# LEDs.net
KiCad netlist of a schematic drawn in Altium Designer
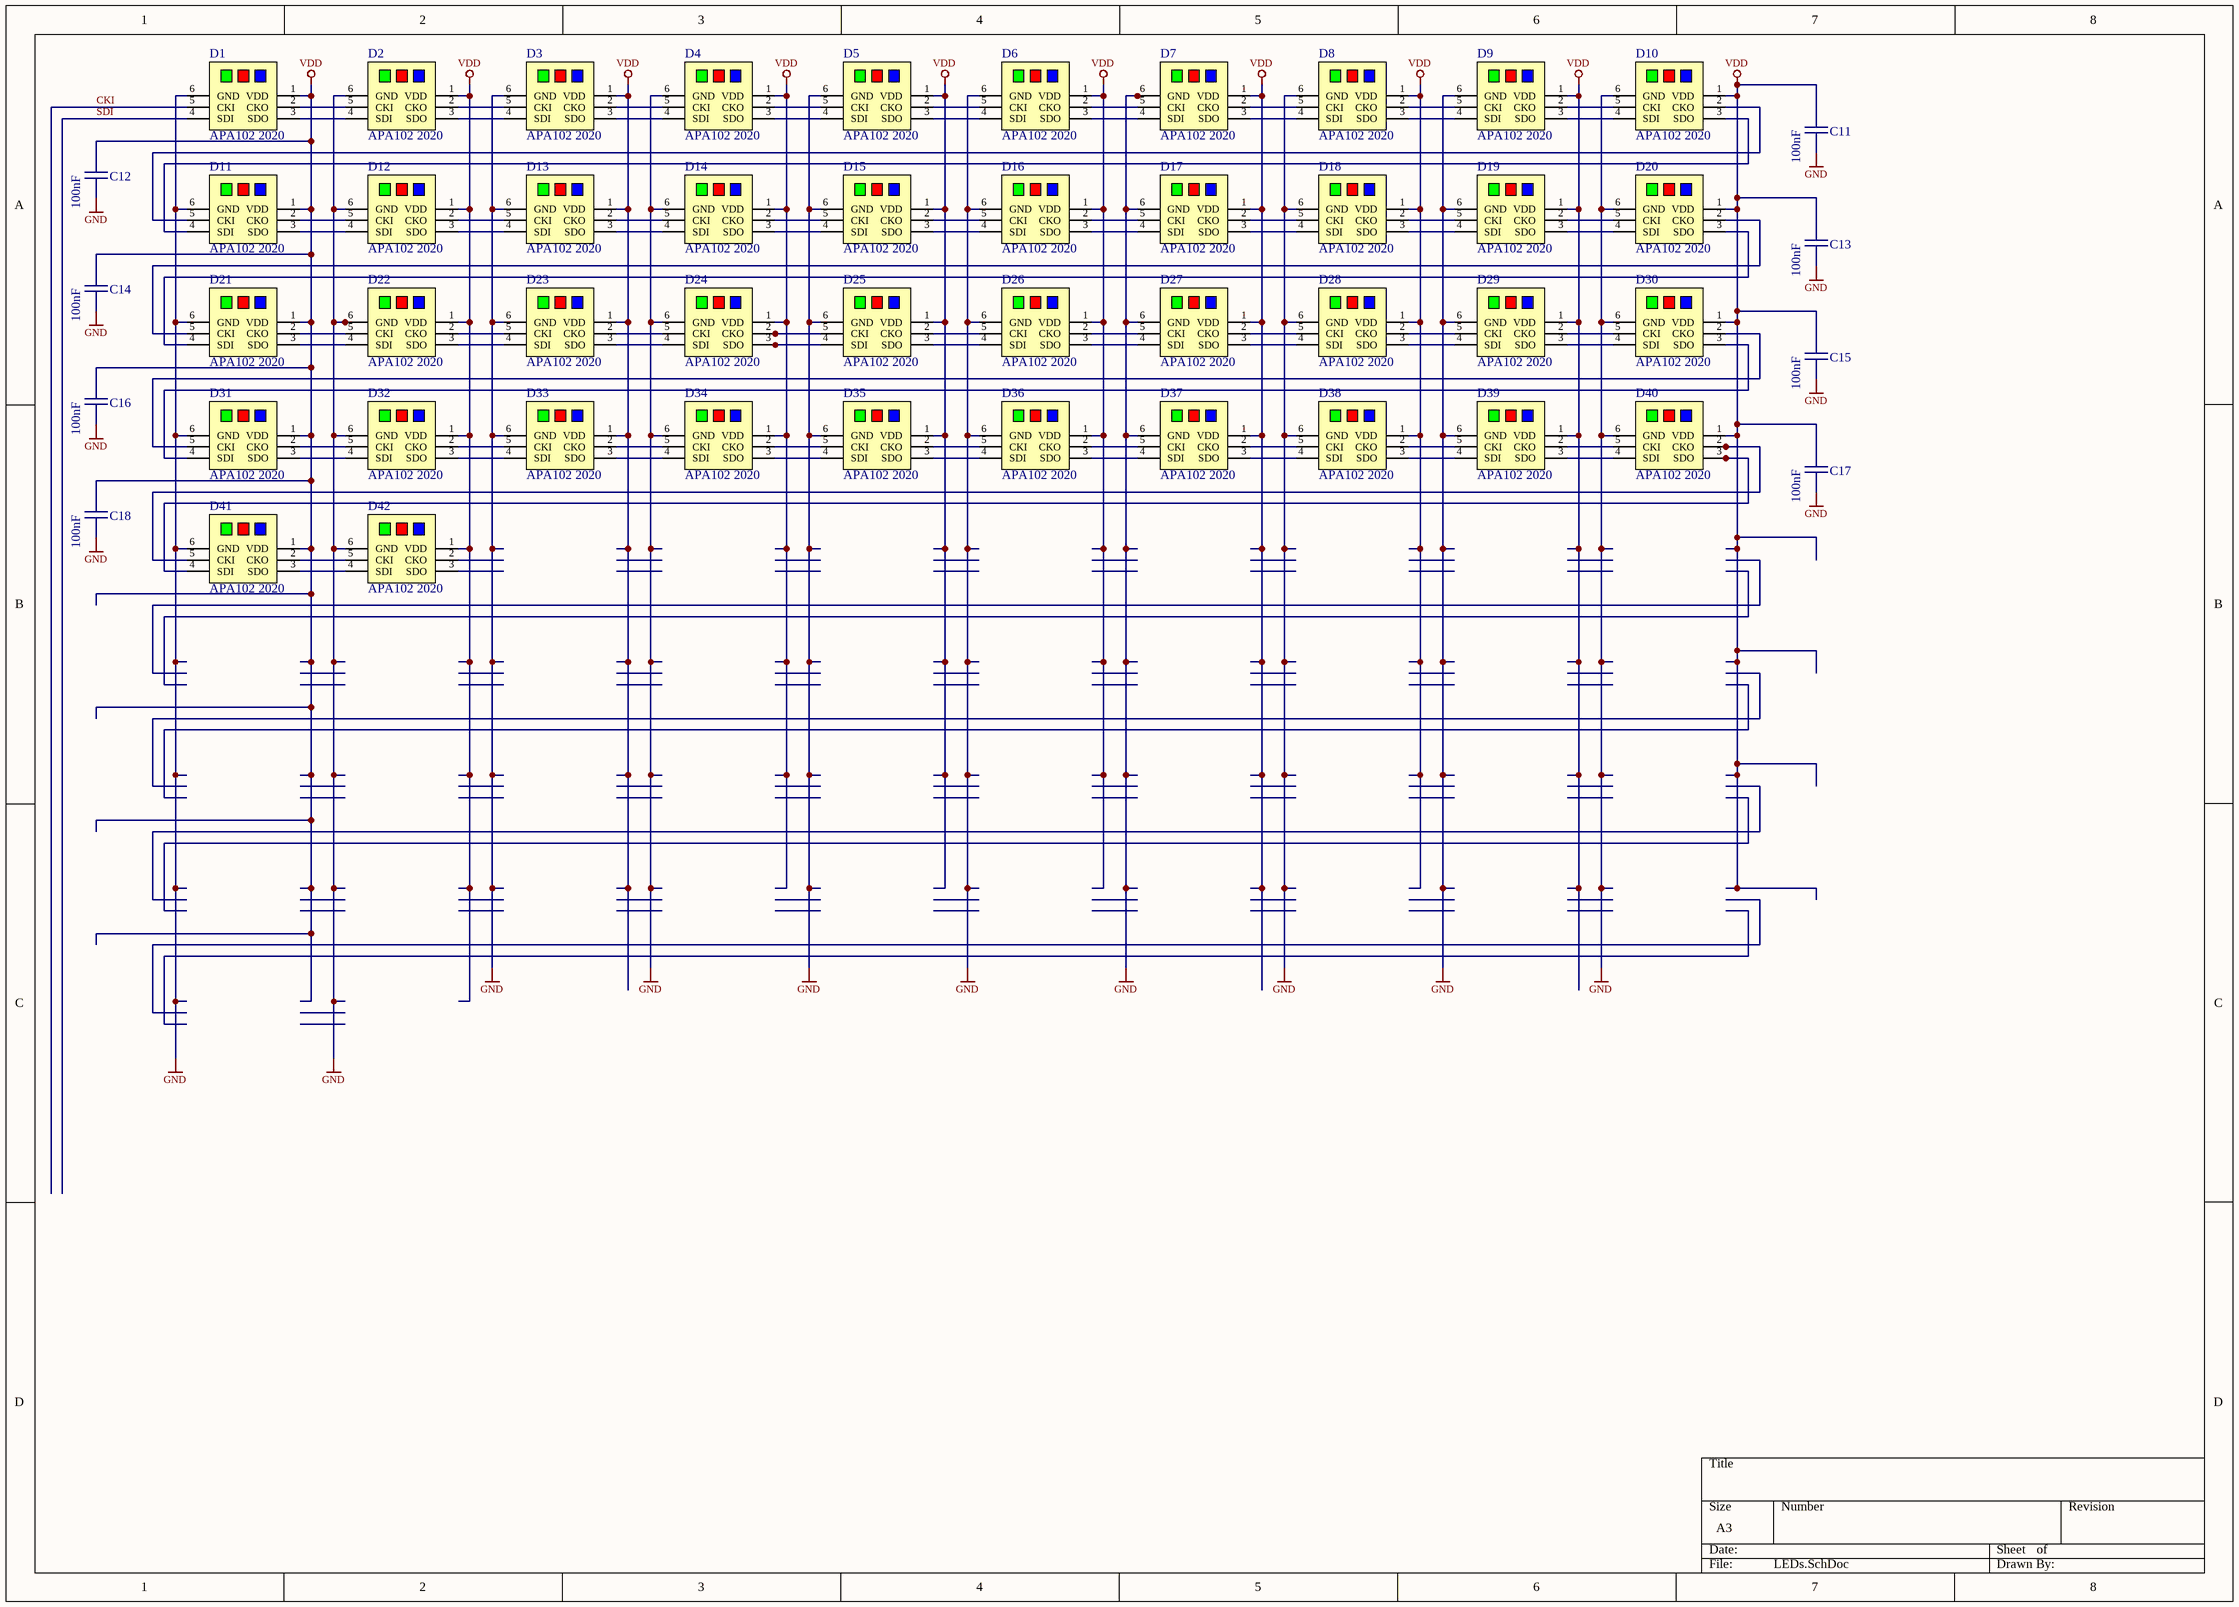
[diagram p0: LEDs.SchDoc]

(export (version "E")
  (design (tool "Eeschema 10.0.6"))
  (components
    (comp (ref "C11")
      (value "100nF")
      (footprint "CAPC0603(1608)55_N")
      (libsource (lib "OVLib_64") (part "CAP"))
    )
    (comp (ref "C12")
      (value "100nF")
      (footprint "CAPC0603(1608)55_N")
      (libsource (lib "OVLib_64") (part "CAP"))
    )
    (comp (ref "C13")
      (value "100nF")
      (footprint "CAPC0603(1608)55_N")
      (libsource (lib "OVLib_64") (part "CAP"))
    )
    (comp (ref "C14")
      (value "100nF")
      (footprint "CAPC0603(1608)55_N")
      (libsource (lib "OVLib_64") (part "CAP"))
    )
    (comp (ref "C15")
      (value "100nF")
      (footprint "CAPC0603(1608)55_N")
      (libsource (lib "OVLib_64") (part "CAP"))
    )
    (comp (ref "C16")
      (value "100nF")
      (footprint "CAPC0603(1608)55_N")
      (libsource (lib "OVLib_64") (part "CAP"))
    )
    (comp (ref "C17")
      (value "100nF")
      (footprint "CAPC0603(1608)55_N")
      (libsource (lib "OVLib_64") (part "CAP"))
    )
    (comp (ref "C18")
      (value "100nF")
      (footprint "CAPC0603(1608)55_N")
      (libsource (lib "OVLib_64") (part "CAP"))
    )
    (comp (ref "D1")
      (value "APA102 2020")
      (footprint "APA_RGB_LED_2020")
      (libsource (lib "OVLib_64") (part "LED_RGB_APA102"))
    )
    (comp (ref "D2")
      (value "APA102 2020")
      (footprint "APA_RGB_LED_2020")
      (libsource (lib "OVLib_64") (part "LED_RGB_APA102"))
    )
    (comp (ref "D3")
      (value "APA102 2020")
      (footprint "APA_RGB_LED_2020")
      (libsource (lib "OVLib_64") (part "LED_RGB_APA102"))
    )
    (comp (ref "D4")
      (value "APA102 2020")
      (footprint "APA_RGB_LED_2020")
      (libsource (lib "OVLib_64") (part "LED_RGB_APA102"))
    )
    (comp (ref "D5")
      (value "APA102 2020")
      (footprint "APA_RGB_LED_2020")
      (libsource (lib "OVLib_64") (part "LED_RGB_APA102"))
    )
    (comp (ref "D6")
      (value "APA102 2020")
      (footprint "APA_RGB_LED_2020")
      (libsource (lib "OVLib_64") (part "LED_RGB_APA102"))
    )
    (comp (ref "D7")
      (value "APA102 2020")
      (footprint "APA_RGB_LED_2020")
      (libsource (lib "OVLib_64") (part "LED_RGB_APA102"))
    )
    (comp (ref "D8")
      (value "APA102 2020")
      (footprint "APA_RGB_LED_2020")
      (libsource (lib "OVLib_64") (part "LED_RGB_APA102"))
    )
    (comp (ref "D9")
      (value "APA102 2020")
      (footprint "APA_RGB_LED_2020")
      (libsource (lib "OVLib_64") (part "LED_RGB_APA102"))
    )
    (comp (ref "D10")
      (value "APA102 2020")
      (footprint "APA_RGB_LED_2020")
      (libsource (lib "OVLib_64") (part "LED_RGB_APA102"))
    )
    (comp (ref "D11")
      (value "APA102 2020")
      (footprint "APA_RGB_LED_2020")
      (libsource (lib "OVLib_64") (part "LED_RGB_APA102"))
    )
    (comp (ref "D12")
      (value "APA102 2020")
      (footprint "APA_RGB_LED_2020")
      (libsource (lib "OVLib_64") (part "LED_RGB_APA102"))
    )
    (comp (ref "D13")
      (value "APA102 2020")
      (footprint "APA_RGB_LED_2020")
      (libsource (lib "OVLib_64") (part "LED_RGB_APA102"))
    )
    (comp (ref "D14")
      (value "APA102 2020")
      (footprint "APA_RGB_LED_2020")
      (libsource (lib "OVLib_64") (part "LED_RGB_APA102"))
    )
    (comp (ref "D15")
      (value "APA102 2020")
      (footprint "APA_RGB_LED_2020")
      (libsource (lib "OVLib_64") (part "LED_RGB_APA102"))
    )
    (comp (ref "D16")
      (value "APA102 2020")
      (footprint "APA_RGB_LED_2020")
      (libsource (lib "OVLib_64") (part "LED_RGB_APA102"))
    )
    (comp (ref "D17")
      (value "APA102 2020")
      (footprint "APA_RGB_LED_2020")
      (libsource (lib "OVLib_64") (part "LED_RGB_APA102"))
    )
    (comp (ref "D18")
      (value "APA102 2020")
      (footprint "APA_RGB_LED_2020")
      (libsource (lib "OVLib_64") (part "LED_RGB_APA102"))
    )
    (comp (ref "D19")
      (value "APA102 2020")
      (footprint "APA_RGB_LED_2020")
      (libsource (lib "OVLib_64") (part "LED_RGB_APA102"))
    )
    (comp (ref "D20")
      (value "APA102 2020")
      (footprint "APA_RGB_LED_2020")
      (libsource (lib "OVLib_64") (part "LED_RGB_APA102"))
    )
    (comp (ref "D21")
      (value "APA102 2020")
      (footprint "APA_RGB_LED_2020")
      (libsource (lib "OVLib_64") (part "LED_RGB_APA102"))
    )
    (comp (ref "D22")
      (value "APA102 2020")
      (footprint "APA_RGB_LED_2020")
      (libsource (lib "OVLib_64") (part "LED_RGB_APA102"))
    )
    (comp (ref "D23")
      (value "APA102 2020")
      (footprint "APA_RGB_LED_2020")
      (libsource (lib "OVLib_64") (part "LED_RGB_APA102"))
    )
    (comp (ref "D24")
      (value "APA102 2020")
      (footprint "APA_RGB_LED_2020")
      (libsource (lib "OVLib_64") (part "LED_RGB_APA102"))
    )
    (comp (ref "D25")
      (value "APA102 2020")
      (footprint "APA_RGB_LED_2020")
      (libsource (lib "OVLib_64") (part "LED_RGB_APA102"))
    )
    (comp (ref "D26")
      (value "APA102 2020")
      (footprint "APA_RGB_LED_2020")
      (libsource (lib "OVLib_64") (part "LED_RGB_APA102"))
    )
    (comp (ref "D27")
      (value "APA102 2020")
      (footprint "APA_RGB_LED_2020")
      (libsource (lib "OVLib_64") (part "LED_RGB_APA102"))
    )
    (comp (ref "D28")
      (value "APA102 2020")
      (footprint "APA_RGB_LED_2020")
      (libsource (lib "OVLib_64") (part "LED_RGB_APA102"))
    )
    (comp (ref "D29")
      (value "APA102 2020")
      (footprint "APA_RGB_LED_2020")
      (libsource (lib "OVLib_64") (part "LED_RGB_APA102"))
    )
    (comp (ref "D30")
      (value "APA102 2020")
      (footprint "APA_RGB_LED_2020")
      (libsource (lib "OVLib_64") (part "LED_RGB_APA102"))
    )
    (comp (ref "D31")
      (value "APA102 2020")
      (footprint "APA_RGB_LED_2020")
      (libsource (lib "OVLib_64") (part "LED_RGB_APA102"))
    )
    (comp (ref "D32")
      (value "APA102 2020")
      (footprint "APA_RGB_LED_2020")
      (libsource (lib "OVLib_64") (part "LED_RGB_APA102"))
    )
    (comp (ref "D33")
      (value "APA102 2020")
      (footprint "APA_RGB_LED_2020")
      (libsource (lib "OVLib_64") (part "LED_RGB_APA102"))
    )
    (comp (ref "D34")
      (value "APA102 2020")
      (footprint "APA_RGB_LED_2020")
      (libsource (lib "OVLib_64") (part "LED_RGB_APA102"))
    )
    (comp (ref "D35")
      (value "APA102 2020")
      (footprint "APA_RGB_LED_2020")
      (libsource (lib "OVLib_64") (part "LED_RGB_APA102"))
    )
    (comp (ref "D36")
      (value "APA102 2020")
      (footprint "APA_RGB_LED_2020")
      (libsource (lib "OVLib_64") (part "LED_RGB_APA102"))
    )
    (comp (ref "D37")
      (value "APA102 2020")
      (footprint "APA_RGB_LED_2020")
      (libsource (lib "OVLib_64") (part "LED_RGB_APA102"))
    )
    (comp (ref "D38")
      (value "APA102 2020")
      (footprint "APA_RGB_LED_2020")
      (libsource (lib "OVLib_64") (part "LED_RGB_APA102"))
    )
    (comp (ref "D39")
      (value "APA102 2020")
      (footprint "APA_RGB_LED_2020")
      (libsource (lib "OVLib_64") (part "LED_RGB_APA102"))
    )
    (comp (ref "D40")
      (value "APA102 2020")
      (footprint "APA_RGB_LED_2020")
      (libsource (lib "OVLib_64") (part "LED_RGB_APA102"))
    )
    (comp (ref "D41")
      (value "APA102 2020")
      (footprint "APA_RGB_LED_2020")
      (libsource (lib "OVLib_64") (part "LED_RGB_APA102"))
    )
    (comp (ref "D42")
      (value "APA102 2020")
      (footprint "APA_RGB_LED_2020")
      (libsource (lib "OVLib_64") (part "LED_RGB_APA102"))
    )
  )
  (nets
    (net (code "1") (name "/CKI") (class "Default")
      (node (ref "D1") (pin "5") (pinfunction "CKI_5") (pintype "passive"))
    )
    (net (code "2") (name "/SDI") (class "Default")
      (node (ref "D1") (pin "4") (pinfunction "SDI_4") (pintype "passive"))
    )
    (net (code "3") (name "GND") (class "Default")
      (node (ref "C11") (pin "1") (pinfunction "1_1") (pintype "passive"))
      (node (ref "C12") (pin "1") (pinfunction "1_1") (pintype "passive"))
      (node (ref "C13") (pin "1") (pinfunction "1_1") (pintype "passive"))
      (node (ref "C14") (pin "1") (pinfunction "1_1") (pintype "passive"))
      (node (ref "C15") (pin "1") (pinfunction "1_1") (pintype "passive"))
      (node (ref "C16") (pin "1") (pinfunction "1_1") (pintype "passive"))
      (node (ref "C17") (pin "1") (pinfunction "1_1") (pintype "passive"))
      (node (ref "C18") (pin "1") (pinfunction "1_1") (pintype "passive"))
      (node (ref "D1") (pin "6") (pinfunction "GND_6") (pintype "passive"))
      (node (ref "D10") (pin "6") (pinfunction "GND_6") (pintype "passive"))
      (node (ref "D11") (pin "6") (pinfunction "GND_6") (pintype "passive"))
      (node (ref "D12") (pin "6") (pinfunction "GND_6") (pintype "passive"))
      (node (ref "D13") (pin "6") (pinfunction "GND_6") (pintype "passive"))
      (node (ref "D14") (pin "6") (pinfunction "GND_6") (pintype "passive"))
      (node (ref "D15") (pin "6") (pinfunction "GND_6") (pintype "passive"))
      (node (ref "D16") (pin "6") (pinfunction "GND_6") (pintype "passive"))
      (node (ref "D17") (pin "6") (pinfunction "GND_6") (pintype "passive"))
      (node (ref "D18") (pin "6") (pinfunction "GND_6") (pintype "passive"))
      (node (ref "D19") (pin "6") (pinfunction "GND_6") (pintype "passive"))
      (node (ref "D2") (pin "6") (pinfunction "GND_6") (pintype "passive"))
      (node (ref "D20") (pin "6") (pinfunction "GND_6") (pintype "passive"))
      (node (ref "D21") (pin "6") (pinfunction "GND_6") (pintype "passive"))
      (node (ref "D22") (pin "6") (pinfunction "GND_6") (pintype "passive"))
      (node (ref "D23") (pin "6") (pinfunction "GND_6") (pintype "passive"))
      (node (ref "D24") (pin "6") (pinfunction "GND_6") (pintype "passive"))
      (node (ref "D25") (pin "6") (pinfunction "GND_6") (pintype "passive"))
      (node (ref "D26") (pin "6") (pinfunction "GND_6") (pintype "passive"))
      (node (ref "D27") (pin "6") (pinfunction "GND_6") (pintype "passive"))
      (node (ref "D28") (pin "6") (pinfunction "GND_6") (pintype "passive"))
      (node (ref "D29") (pin "6") (pinfunction "GND_6") (pintype "passive"))
      (node (ref "D3") (pin "6") (pinfunction "GND_6") (pintype "passive"))
      (node (ref "D30") (pin "6") (pinfunction "GND_6") (pintype "passive"))
      (node (ref "D31") (pin "6") (pinfunction "GND_6") (pintype "passive"))
      (node (ref "D32") (pin "6") (pinfunction "GND_6") (pintype "passive"))
      (node (ref "D33") (pin "6") (pinfunction "GND_6") (pintype "passive"))
      (node (ref "D34") (pin "6") (pinfunction "GND_6") (pintype "passive"))
      (node (ref "D35") (pin "6") (pinfunction "GND_6") (pintype "passive"))
      (node (ref "D36") (pin "6") (pinfunction "GND_6") (pintype "passive"))
      (node (ref "D37") (pin "6") (pinfunction "GND_6") (pintype "passive"))
      (node (ref "D38") (pin "6") (pinfunction "GND_6") (pintype "passive"))
      (node (ref "D39") (pin "6") (pinfunction "GND_6") (pintype "passive"))
      (node (ref "D4") (pin "6") (pinfunction "GND_6") (pintype "passive"))
      (node (ref "D40") (pin "6") (pinfunction "GND_6") (pintype "passive"))
      (node (ref "D41") (pin "6") (pinfunction "GND_6") (pintype "passive"))
      (node (ref "D42") (pin "6") (pinfunction "GND_6") (pintype "passive"))
      (node (ref "D5") (pin "6") (pinfunction "GND_6") (pintype "passive"))
      (node (ref "D6") (pin "6") (pinfunction "GND_6") (pintype "passive"))
      (node (ref "D7") (pin "6") (pinfunction "GND_6") (pintype "passive"))
      (node (ref "D8") (pin "6") (pinfunction "GND_6") (pintype "passive"))
      (node (ref "D9") (pin "6") (pinfunction "GND_6") (pintype "passive"))
    )
    (net (code "4") (name "Net-(D1-CKO)") (class "Default")
      (node (ref "D1") (pin "2") (pinfunction "CKO_2") (pintype "passive"))
      (node (ref "D2") (pin "5") (pinfunction "CKI_5") (pintype "passive"))
    )
    (net (code "5") (name "Net-(D1-SDO)") (class "Default")
      (node (ref "D1") (pin "3") (pinfunction "SDO_3") (pintype "passive"))
      (node (ref "D2") (pin "4") (pinfunction "SDI_4") (pintype "passive"))
    )
    (net (code "6") (name "Net-(D2-CKO)") (class "Default")
      (node (ref "D2") (pin "2") (pinfunction "CKO_2") (pintype "passive"))
      (node (ref "D3") (pin "5") (pinfunction "CKI_5") (pintype "passive"))
    )
    (net (code "7") (name "Net-(D2-SDO)") (class "Default")
      (node (ref "D2") (pin "3") (pinfunction "SDO_3") (pintype "passive"))
      (node (ref "D3") (pin "4") (pinfunction "SDI_4") (pintype "passive"))
    )
    (net (code "8") (name "Net-(D3-CKO)") (class "Default")
      (node (ref "D3") (pin "2") (pinfunction "CKO_2") (pintype "passive"))
      (node (ref "D4") (pin "5") (pinfunction "CKI_5") (pintype "passive"))
    )
    (net (code "9") (name "Net-(D3-SDO)") (class "Default")
      (node (ref "D3") (pin "3") (pinfunction "SDO_3") (pintype "passive"))
      (node (ref "D4") (pin "4") (pinfunction "SDI_4") (pintype "passive"))
    )
    (net (code "10") (name "Net-(D4-CKO)") (class "Default")
      (node (ref "D4") (pin "2") (pinfunction "CKO_2") (pintype "passive"))
      (node (ref "D5") (pin "5") (pinfunction "CKI_5") (pintype "passive"))
    )
    (net (code "11") (name "Net-(D4-SDO)") (class "Default")
      (node (ref "D4") (pin "3") (pinfunction "SDO_3") (pintype "passive"))
      (node (ref "D5") (pin "4") (pinfunction "SDI_4") (pintype "passive"))
    )
    (net (code "12") (name "Net-(D5-CKO)") (class "Default")
      (node (ref "D5") (pin "2") (pinfunction "CKO_2") (pintype "passive"))
      (node (ref "D6") (pin "5") (pinfunction "CKI_5") (pintype "passive"))
    )
    (net (code "13") (name "Net-(D5-SDO)") (class "Default")
      (node (ref "D5") (pin "3") (pinfunction "SDO_3") (pintype "passive"))
      (node (ref "D6") (pin "4") (pinfunction "SDI_4") (pintype "passive"))
    )
    (net (code "14") (name "Net-(D6-CKO)") (class "Default")
      (node (ref "D6") (pin "2") (pinfunction "CKO_2") (pintype "passive"))
      (node (ref "D7") (pin "5") (pinfunction "CKI_5") (pintype "passive"))
    )
    (net (code "15") (name "Net-(D6-SDO)") (class "Default")
      (node (ref "D6") (pin "3") (pinfunction "SDO_3") (pintype "passive"))
      (node (ref "D7") (pin "4") (pinfunction "SDI_4") (pintype "passive"))
    )
    (net (code "16") (name "Net-(D7-CKO)") (class "Default")
      (node (ref "D7") (pin "2") (pinfunction "CKO_2") (pintype "passive"))
      (node (ref "D8") (pin "5") (pinfunction "CKI_5") (pintype "passive"))
    )
    (net (code "17") (name "Net-(D7-SDO)") (class "Default")
      (node (ref "D7") (pin "3") (pinfunction "SDO_3") (pintype "passive"))
      (node (ref "D8") (pin "4") (pinfunction "SDI_4") (pintype "passive"))
    )
    (net (code "18") (name "Net-(D8-CKO)") (class "Default")
      (node (ref "D8") (pin "2") (pinfunction "CKO_2") (pintype "passive"))
      (node (ref "D9") (pin "5") (pinfunction "CKI_5") (pintype "passive"))
    )
    (net (code "19") (name "Net-(D8-SDO)") (class "Default")
      (node (ref "D8") (pin "3") (pinfunction "SDO_3") (pintype "passive"))
      (node (ref "D9") (pin "4") (pinfunction "SDI_4") (pintype "passive"))
    )
    (net (code "20") (name "Net-(D10-CKI)") (class "Default")
      (node (ref "D10") (pin "5") (pinfunction "CKI_5") (pintype "passive"))
      (node (ref "D9") (pin "2") (pinfunction "CKO_2") (pintype "passive"))
    )
    (net (code "21") (name "Net-(D10-CKO)") (class "Default")
      (node (ref "D10") (pin "2") (pinfunction "CKO_2") (pintype "passive"))
      (node (ref "D11") (pin "5") (pinfunction "CKI_5") (pintype "passive"))
    )
    (net (code "22") (name "Net-(D10-SDI)") (class "Default")
      (node (ref "D10") (pin "4") (pinfunction "SDI_4") (pintype "passive"))
      (node (ref "D9") (pin "3") (pinfunction "SDO_3") (pintype "passive"))
    )
    (net (code "23") (name "Net-(D10-SDO)") (class "Default")
      (node (ref "D10") (pin "3") (pinfunction "SDO_3") (pintype "passive"))
      (node (ref "D11") (pin "4") (pinfunction "SDI_4") (pintype "passive"))
    )
    (net (code "24") (name "Net-(D11-CKO)") (class "Default")
      (node (ref "D11") (pin "2") (pinfunction "CKO_2") (pintype "passive"))
      (node (ref "D12") (pin "5") (pinfunction "CKI_5") (pintype "passive"))
    )
    (net (code "25") (name "Net-(D11-SDO)") (class "Default")
      (node (ref "D11") (pin "3") (pinfunction "SDO_3") (pintype "passive"))
      (node (ref "D12") (pin "4") (pinfunction "SDI_4") (pintype "passive"))
    )
    (net (code "26") (name "Net-(D12-CKO)") (class "Default")
      (node (ref "D12") (pin "2") (pinfunction "CKO_2") (pintype "passive"))
      (node (ref "D13") (pin "5") (pinfunction "CKI_5") (pintype "passive"))
    )
    (net (code "27") (name "Net-(D12-SDO)") (class "Default")
      (node (ref "D12") (pin "3") (pinfunction "SDO_3") (pintype "passive"))
      (node (ref "D13") (pin "4") (pinfunction "SDI_4") (pintype "passive"))
    )
    (net (code "28") (name "Net-(D13-CKO)") (class "Default")
      (node (ref "D13") (pin "2") (pinfunction "CKO_2") (pintype "passive"))
      (node (ref "D14") (pin "5") (pinfunction "CKI_5") (pintype "passive"))
    )
    (net (code "29") (name "Net-(D13-SDO)") (class "Default")
      (node (ref "D13") (pin "3") (pinfunction "SDO_3") (pintype "passive"))
      (node (ref "D14") (pin "4") (pinfunction "SDI_4") (pintype "passive"))
    )
    (net (code "30") (name "Net-(D14-CKO)") (class "Default")
      (node (ref "D14") (pin "2") (pinfunction "CKO_2") (pintype "passive"))
      (node (ref "D15") (pin "5") (pinfunction "CKI_5") (pintype "passive"))
    )
    (net (code "31") (name "Net-(D14-SDO)") (class "Default")
      (node (ref "D14") (pin "3") (pinfunction "SDO_3") (pintype "passive"))
      (node (ref "D15") (pin "4") (pinfunction "SDI_4") (pintype "passive"))
    )
    (net (code "32") (name "Net-(D15-CKO)") (class "Default")
      (node (ref "D15") (pin "2") (pinfunction "CKO_2") (pintype "passive"))
      (node (ref "D16") (pin "5") (pinfunction "CKI_5") (pintype "passive"))
    )
    (net (code "33") (name "Net-(D15-SDO)") (class "Default")
      (node (ref "D15") (pin "3") (pinfunction "SDO_3") (pintype "passive"))
      (node (ref "D16") (pin "4") (pinfunction "SDI_4") (pintype "passive"))
    )
    (net (code "34") (name "Net-(D16-CKO)") (class "Default")
      (node (ref "D16") (pin "2") (pinfunction "CKO_2") (pintype "passive"))
      (node (ref "D17") (pin "5") (pinfunction "CKI_5") (pintype "passive"))
    )
    (net (code "35") (name "Net-(D16-SDO)") (class "Default")
      (node (ref "D16") (pin "3") (pinfunction "SDO_3") (pintype "passive"))
      (node (ref "D17") (pin "4") (pinfunction "SDI_4") (pintype "passive"))
    )
    (net (code "36") (name "Net-(D17-CKO)") (class "Default")
      (node (ref "D17") (pin "2") (pinfunction "CKO_2") (pintype "passive"))
      (node (ref "D18") (pin "5") (pinfunction "CKI_5") (pintype "passive"))
    )
    (net (code "37") (name "Net-(D17-SDO)") (class "Default")
      (node (ref "D17") (pin "3") (pinfunction "SDO_3") (pintype "passive"))
      (node (ref "D18") (pin "4") (pinfunction "SDI_4") (pintype "passive"))
    )
    (net (code "38") (name "Net-(D18-CKO)") (class "Default")
      (node (ref "D18") (pin "2") (pinfunction "CKO_2") (pintype "passive"))
      (node (ref "D19") (pin "5") (pinfunction "CKI_5") (pintype "passive"))
    )
    (net (code "39") (name "Net-(D18-SDO)") (class "Default")
      (node (ref "D18") (pin "3") (pinfunction "SDO_3") (pintype "passive"))
      (node (ref "D19") (pin "4") (pinfunction "SDI_4") (pintype "passive"))
    )
    (net (code "40") (name "Net-(D19-CKO)") (class "Default")
      (node (ref "D19") (pin "2") (pinfunction "CKO_2") (pintype "passive"))
      (node (ref "D20") (pin "5") (pinfunction "CKI_5") (pintype "passive"))
    )
    (net (code "41") (name "Net-(D19-SDO)") (class "Default")
      (node (ref "D19") (pin "3") (pinfunction "SDO_3") (pintype "passive"))
      (node (ref "D20") (pin "4") (pinfunction "SDI_4") (pintype "passive"))
    )
    (net (code "42") (name "Net-(D20-CKO)") (class "Default")
      (node (ref "D20") (pin "2") (pinfunction "CKO_2") (pintype "passive"))
      (node (ref "D21") (pin "5") (pinfunction "CKI_5") (pintype "passive"))
    )
    (net (code "43") (name "Net-(D20-SDO)") (class "Default")
      (node (ref "D20") (pin "3") (pinfunction "SDO_3") (pintype "passive"))
      (node (ref "D21") (pin "4") (pinfunction "SDI_4") (pintype "passive"))
    )
    (net (code "44") (name "Net-(D21-CKO)") (class "Default")
      (node (ref "D21") (pin "2") (pinfunction "CKO_2") (pintype "passive"))
      (node (ref "D22") (pin "5") (pinfunction "CKI_5") (pintype "passive"))
    )
    (net (code "45") (name "Net-(D21-SDO)") (class "Default")
      (node (ref "D21") (pin "3") (pinfunction "SDO_3") (pintype "passive"))
      (node (ref "D22") (pin "4") (pinfunction "SDI_4") (pintype "passive"))
    )
    (net (code "46") (name "Net-(D22-CKO)") (class "Default")
      (node (ref "D22") (pin "2") (pinfunction "CKO_2") (pintype "passive"))
      (node (ref "D23") (pin "5") (pinfunction "CKI_5") (pintype "passive"))
    )
    (net (code "47") (name "Net-(D22-SDO)") (class "Default")
      (node (ref "D22") (pin "3") (pinfunction "SDO_3") (pintype "passive"))
      (node (ref "D23") (pin "4") (pinfunction "SDI_4") (pintype "passive"))
    )
    (net (code "48") (name "Net-(D23-CKO)") (class "Default")
      (node (ref "D23") (pin "2") (pinfunction "CKO_2") (pintype "passive"))
      (node (ref "D24") (pin "5") (pinfunction "CKI_5") (pintype "passive"))
    )
    (net (code "49") (name "Net-(D23-SDO)") (class "Default")
      (node (ref "D23") (pin "3") (pinfunction "SDO_3") (pintype "passive"))
      (node (ref "D24") (pin "4") (pinfunction "SDI_4") (pintype "passive"))
    )
    (net (code "50") (name "Net-(D24-CKO)") (class "Default")
      (node (ref "D24") (pin "2") (pinfunction "CKO_2") (pintype "passive"))
      (node (ref "D25") (pin "5") (pinfunction "CKI_5") (pintype "passive"))
    )
    (net (code "51") (name "Net-(D24-SDO)") (class "Default")
      (node (ref "D24") (pin "3") (pinfunction "SDO_3") (pintype "passive"))
      (node (ref "D25") (pin "4") (pinfunction "SDI_4") (pintype "passive"))
    )
    (net (code "52") (name "Net-(D25-CKO)") (class "Default")
      (node (ref "D25") (pin "2") (pinfunction "CKO_2") (pintype "passive"))
      (node (ref "D26") (pin "5") (pinfunction "CKI_5") (pintype "passive"))
    )
    (net (code "53") (name "Net-(D25-SDO)") (class "Default")
      (node (ref "D25") (pin "3") (pinfunction "SDO_3") (pintype "passive"))
      (node (ref "D26") (pin "4") (pinfunction "SDI_4") (pintype "passive"))
    )
    (net (code "54") (name "Net-(D26-CKO)") (class "Default")
      (node (ref "D26") (pin "2") (pinfunction "CKO_2") (pintype "passive"))
      (node (ref "D27") (pin "5") (pinfunction "CKI_5") (pintype "passive"))
    )
    (net (code "55") (name "Net-(D26-SDO)") (class "Default")
      (node (ref "D26") (pin "3") (pinfunction "SDO_3") (pintype "passive"))
      (node (ref "D27") (pin "4") (pinfunction "SDI_4") (pintype "passive"))
    )
    (net (code "56") (name "Net-(D27-CKO)") (class "Default")
      (node (ref "D27") (pin "2") (pinfunction "CKO_2") (pintype "passive"))
      (node (ref "D28") (pin "5") (pinfunction "CKI_5") (pintype "passive"))
    )
    (net (code "57") (name "Net-(D27-SDO)") (class "Default")
      (node (ref "D27") (pin "3") (pinfunction "SDO_3") (pintype "passive"))
      (node (ref "D28") (pin "4") (pinfunction "SDI_4") (pintype "passive"))
    )
    (net (code "58") (name "Net-(D28-CKO)") (class "Default")
      (node (ref "D28") (pin "2") (pinfunction "CKO_2") (pintype "passive"))
      (node (ref "D29") (pin "5") (pinfunction "CKI_5") (pintype "passive"))
    )
    (net (code "59") (name "Net-(D28-SDO)") (class "Default")
      (node (ref "D28") (pin "3") (pinfunction "SDO_3") (pintype "passive"))
      (node (ref "D29") (pin "4") (pinfunction "SDI_4") (pintype "passive"))
    )
    (net (code "60") (name "Net-(D29-CKO)") (class "Default")
      (node (ref "D29") (pin "2") (pinfunction "CKO_2") (pintype "passive"))
      (node (ref "D30") (pin "5") (pinfunction "CKI_5") (pintype "passive"))
    )
    (net (code "61") (name "Net-(D29-SDO)") (class "Default")
      (node (ref "D29") (pin "3") (pinfunction "SDO_3") (pintype "passive"))
      (node (ref "D30") (pin "4") (pinfunction "SDI_4") (pintype "passive"))
    )
    (net (code "62") (name "Net-(D30-CKO)") (class "Default")
      (node (ref "D30") (pin "2") (pinfunction "CKO_2") (pintype "passive"))
      (node (ref "D31") (pin "5") (pinfunction "CKI_5") (pintype "passive"))
    )
    (net (code "63") (name "Net-(D30-SDO)") (class "Default")
      (node (ref "D30") (pin "3") (pinfunction "SDO_3") (pintype "passive"))
      (node (ref "D31") (pin "4") (pinfunction "SDI_4") (pintype "passive"))
    )
    (net (code "64") (name "Net-(D31-CKO)") (class "Default")
      (node (ref "D31") (pin "2") (pinfunction "CKO_2") (pintype "passive"))
      (node (ref "D32") (pin "5") (pinfunction "CKI_5") (pintype "passive"))
    )
    (net (code "65") (name "Net-(D31-SDO)") (class "Default")
      (node (ref "D31") (pin "3") (pinfunction "SDO_3") (pintype "passive"))
      (node (ref "D32") (pin "4") (pinfunction "SDI_4") (pintype "passive"))
    )
    (net (code "66") (name "Net-(D32-CKO)") (class "Default")
      (node (ref "D32") (pin "2") (pinfunction "CKO_2") (pintype "passive"))
      (node (ref "D33") (pin "5") (pinfunction "CKI_5") (pintype "passive"))
    )
    (net (code "67") (name "Net-(D32-SDO)") (class "Default")
      (node (ref "D32") (pin "3") (pinfunction "SDO_3") (pintype "passive"))
      (node (ref "D33") (pin "4") (pinfunction "SDI_4") (pintype "passive"))
    )
    (net (code "68") (name "Net-(D33-CKO)") (class "Default")
      (node (ref "D33") (pin "2") (pinfunction "CKO_2") (pintype "passive"))
      (node (ref "D34") (pin "5") (pinfunction "CKI_5") (pintype "passive"))
    )
    (net (code "69") (name "Net-(D33-SDO)") (class "Default")
      (node (ref "D33") (pin "3") (pinfunction "SDO_3") (pintype "passive"))
      (node (ref "D34") (pin "4") (pinfunction "SDI_4") (pintype "passive"))
    )
    (net (code "70") (name "Net-(D34-CKO)") (class "Default")
      (node (ref "D34") (pin "2") (pinfunction "CKO_2") (pintype "passive"))
      (node (ref "D35") (pin "5") (pinfunction "CKI_5") (pintype "passive"))
    )
    (net (code "71") (name "Net-(D34-SDO)") (class "Default")
      (node (ref "D34") (pin "3") (pinfunction "SDO_3") (pintype "passive"))
      (node (ref "D35") (pin "4") (pinfunction "SDI_4") (pintype "passive"))
    )
    (net (code "72") (name "Net-(D35-CKO)") (class "Default")
      (node (ref "D35") (pin "2") (pinfunction "CKO_2") (pintype "passive"))
      (node (ref "D36") (pin "5") (pinfunction "CKI_5") (pintype "passive"))
    )
    (net (code "73") (name "Net-(D35-SDO)") (class "Default")
      (node (ref "D35") (pin "3") (pinfunction "SDO_3") (pintype "passive"))
      (node (ref "D36") (pin "4") (pinfunction "SDI_4") (pintype "passive"))
    )
    (net (code "74") (name "Net-(D36-CKO)") (class "Default")
      (node (ref "D36") (pin "2") (pinfunction "CKO_2") (pintype "passive"))
      (node (ref "D37") (pin "5") (pinfunction "CKI_5") (pintype "passive"))
    )
    (net (code "75") (name "Net-(D36-SDO)") (class "Default")
      (node (ref "D36") (pin "3") (pinfunction "SDO_3") (pintype "passive"))
      (node (ref "D37") (pin "4") (pinfunction "SDI_4") (pintype "passive"))
    )
    (net (code "76") (name "Net-(D37-CKO)") (class "Default")
      (node (ref "D37") (pin "2") (pinfunction "CKO_2") (pintype "passive"))
      (node (ref "D38") (pin "5") (pinfunction "CKI_5") (pintype "passive"))
    )
    (net (code "77") (name "Net-(D37-SDO)") (class "Default")
      (node (ref "D37") (pin "3") (pinfunction "SDO_3") (pintype "passive"))
      (node (ref "D38") (pin "4") (pinfunction "SDI_4") (pintype "passive"))
    )
    (net (code "78") (name "Net-(D38-CKO)") (class "Default")
      (node (ref "D38") (pin "2") (pinfunction "CKO_2") (pintype "passive"))
      (node (ref "D39") (pin "5") (pinfunction "CKI_5") (pintype "passive"))
    )
    (net (code "79") (name "Net-(D38-SDO)") (class "Default")
      (node (ref "D38") (pin "3") (pinfunction "SDO_3") (pintype "passive"))
      (node (ref "D39") (pin "4") (pinfunction "SDI_4") (pintype "passive"))
    )
    (net (code "80") (name "Net-(D39-CKO)") (class "Default")
      (node (ref "D39") (pin "2") (pinfunction "CKO_2") (pintype "passive"))
      (node (ref "D40") (pin "5") (pinfunction "CKI_5") (pintype "passive"))
    )
    (net (code "81") (name "Net-(D39-SDO)") (class "Default")
      (node (ref "D39") (pin "3") (pinfunction "SDO_3") (pintype "passive"))
      (node (ref "D40") (pin "4") (pinfunction "SDI_4") (pintype "passive"))
    )
    (net (code "82") (name "Net-(D40-CKO)") (class "Default")
      (node (ref "D40") (pin "2") (pinfunction "CKO_2") (pintype "passive"))
      (node (ref "D41") (pin "5") (pinfunction "CKI_5") (pintype "passive"))
    )
    (net (code "83") (name "Net-(D40-SDO)") (class "Default")
      (node (ref "D40") (pin "3") (pinfunction "SDO_3") (pintype "passive"))
      (node (ref "D41") (pin "4") (pinfunction "SDI_4") (pintype "passive"))
    )
    (net (code "84") (name "Net-(D41-CKO)") (class "Default")
      (node (ref "D41") (pin "2") (pinfunction "CKO_2") (pintype "passive"))
      (node (ref "D42") (pin "5") (pinfunction "CKI_5") (pintype "passive"))
    )
    (net (code "85") (name "Net-(D41-SDO)") (class "Default")
      (node (ref "D41") (pin "3") (pinfunction "SDO_3") (pintype "passive"))
      (node (ref "D42") (pin "4") (pinfunction "SDI_4") (pintype "passive"))
    )
    (net (code "86") (name "VDD") (class "Default")
      (node (ref "C11") (pin "2") (pinfunction "2_2") (pintype "passive"))
      (node (ref "C12") (pin "2") (pinfunction "2_2") (pintype "passive"))
      (node (ref "C13") (pin "2") (pinfunction "2_2") (pintype "passive"))
      (node (ref "C14") (pin "2") (pinfunction "2_2") (pintype "passive"))
      (node (ref "C15") (pin "2") (pinfunction "2_2") (pintype "passive"))
      (node (ref "C16") (pin "2") (pinfunction "2_2") (pintype "passive"))
      (node (ref "C17") (pin "2") (pinfunction "2_2") (pintype "passive"))
      (node (ref "C18") (pin "2") (pinfunction "2_2") (pintype "passive"))
      (node (ref "D1") (pin "1") (pinfunction "VDD_1") (pintype "passive"))
      (node (ref "D10") (pin "1") (pinfunction "VDD_1") (pintype "passive"))
      (node (ref "D11") (pin "1") (pinfunction "VDD_1") (pintype "passive"))
      (node (ref "D12") (pin "1") (pinfunction "VDD_1") (pintype "passive"))
      (node (ref "D13") (pin "1") (pinfunction "VDD_1") (pintype "passive"))
      (node (ref "D14") (pin "1") (pinfunction "VDD_1") (pintype "passive"))
      (node (ref "D15") (pin "1") (pinfunction "VDD_1") (pintype "passive"))
      (node (ref "D16") (pin "1") (pinfunction "VDD_1") (pintype "passive"))
      (node (ref "D17") (pin "1") (pinfunction "VDD_1") (pintype "passive"))
      (node (ref "D18") (pin "1") (pinfunction "VDD_1") (pintype "passive"))
      (node (ref "D19") (pin "1") (pinfunction "VDD_1") (pintype "passive"))
      (node (ref "D2") (pin "1") (pinfunction "VDD_1") (pintype "passive"))
      (node (ref "D20") (pin "1") (pinfunction "VDD_1") (pintype "passive"))
      (node (ref "D21") (pin "1") (pinfunction "VDD_1") (pintype "passive"))
      (node (ref "D22") (pin "1") (pinfunction "VDD_1") (pintype "passive"))
      (node (ref "D23") (pin "1") (pinfunction "VDD_1") (pintype "passive"))
      (node (ref "D24") (pin "1") (pinfunction "VDD_1") (pintype "passive"))
      (node (ref "D25") (pin "1") (pinfunction "VDD_1") (pintype "passive"))
      (node (ref "D26") (pin "1") (pinfunction "VDD_1") (pintype "passive"))
      (node (ref "D27") (pin "1") (pinfunction "VDD_1") (pintype "passive"))
      (node (ref "D28") (pin "1") (pinfunction "VDD_1") (pintype "passive"))
      (node (ref "D29") (pin "1") (pinfunction "VDD_1") (pintype "passive"))
      (node (ref "D3") (pin "1") (pinfunction "VDD_1") (pintype "passive"))
      (node (ref "D30") (pin "1") (pinfunction "VDD_1") (pintype "passive"))
      (node (ref "D31") (pin "1") (pinfunction "VDD_1") (pintype "passive"))
      (node (ref "D32") (pin "1") (pinfunction "VDD_1") (pintype "passive"))
      (node (ref "D33") (pin "1") (pinfunction "VDD_1") (pintype "passive"))
      (node (ref "D34") (pin "1") (pinfunction "VDD_1") (pintype "passive"))
      (node (ref "D35") (pin "1") (pinfunction "VDD_1") (pintype "passive"))
      (node (ref "D36") (pin "1") (pinfunction "VDD_1") (pintype "passive"))
      (node (ref "D37") (pin "1") (pinfunction "VDD_1") (pintype "passive"))
      (node (ref "D38") (pin "1") (pinfunction "VDD_1") (pintype "passive"))
      (node (ref "D39") (pin "1") (pinfunction "VDD_1") (pintype "passive"))
      (node (ref "D4") (pin "1") (pinfunction "VDD_1") (pintype "passive"))
      (node (ref "D40") (pin "1") (pinfunction "VDD_1") (pintype "passive"))
      (node (ref "D41") (pin "1") (pinfunction "VDD_1") (pintype "passive"))
      (node (ref "D42") (pin "1") (pinfunction "VDD_1") (pintype "passive"))
      (node (ref "D5") (pin "1") (pinfunction "VDD_1") (pintype "passive"))
      (node (ref "D6") (pin "1") (pinfunction "VDD_1") (pintype "passive"))
      (node (ref "D7") (pin "1") (pinfunction "VDD_1") (pintype "passive"))
      (node (ref "D8") (pin "1") (pinfunction "VDD_1") (pintype "passive"))
      (node (ref "D9") (pin "1") (pinfunction "VDD_1") (pintype "passive"))
    )
    (net (code "87") (name "unconnected-(D42-CKO-Pad2)") (class "Default")
      (node (ref "D42") (pin "2") (pinfunction "CKO_2") (pintype "passive"))
    )
    (net (code "88") (name "unconnected-(D42-SDO-Pad3)") (class "Default")
      (node (ref "D42") (pin "3") (pinfunction "SDO_3") (pintype "passive"))
    )
  )
)
